# 4_ETHERNET.net
KiCad netlist of a schematic drawn in Altium Designer
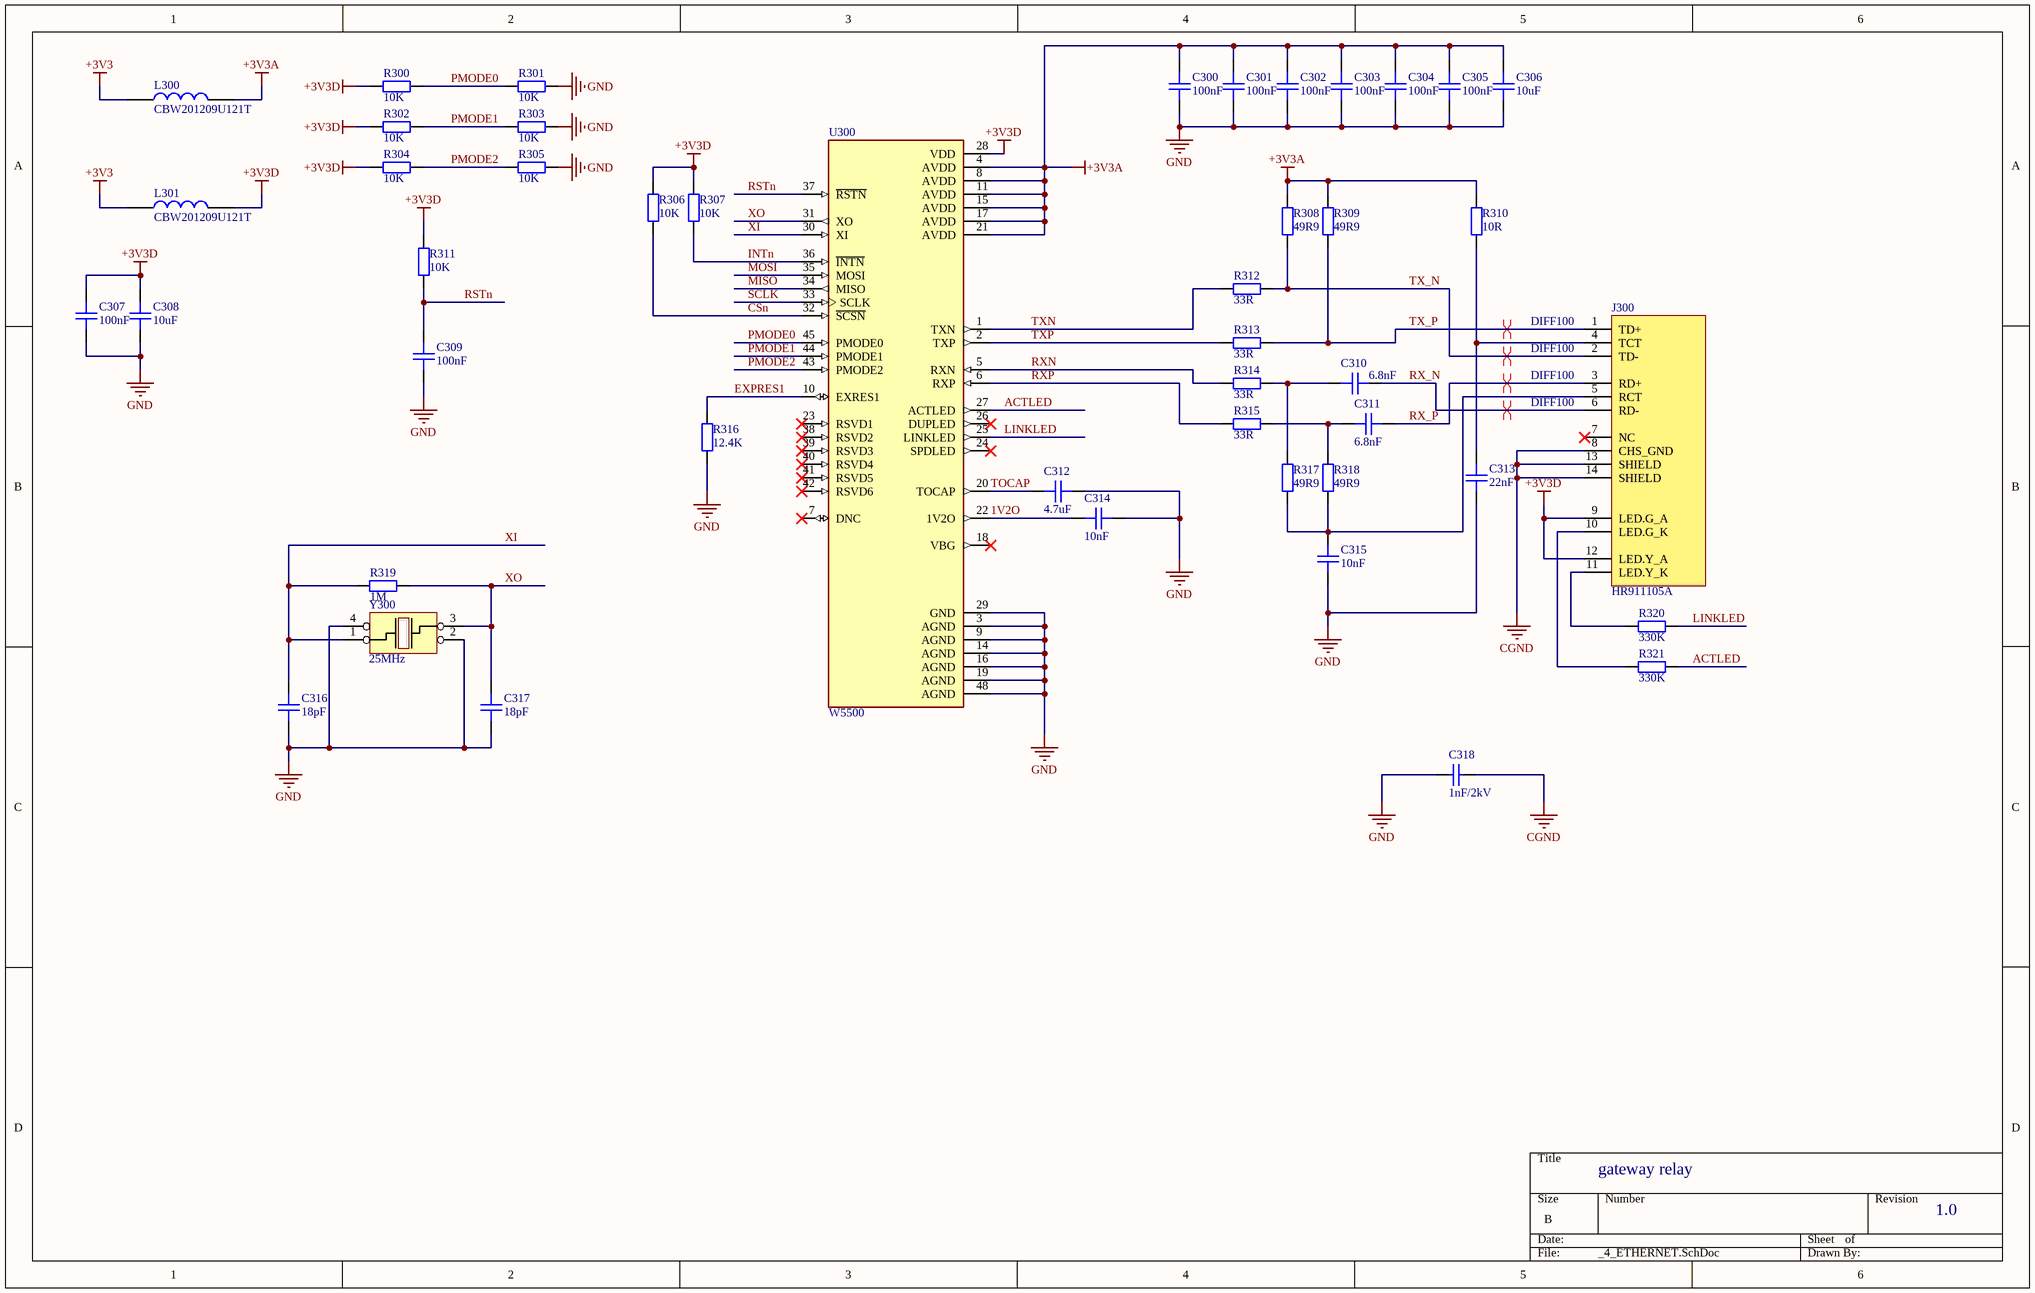
[diagram p0: _4_ETHERNET.SchDoc]

(export (version "E")
  (design (tool "Eeschema 10.0.6"))
  (components
    (comp (ref "C300")
      (value "100nF")
      (footprint "CAPC-0603 (1608)")
      (description "CAP CER 1uF 10% 16V X7R 0603")
      (fields (field (name "MPN") "CC0603KRX7R7BB105"))
      (libsource (lib "BYTECH_HW_LIB_2019") (part "CC0603KRX7R7BB105"))
    )
    (comp (ref "C301")
      (value "100nF")
      (footprint "CAPC-0603 (1608)")
      (description "CAP CER 1uF 10% 16V X7R 0603")
      (fields (field (name "MPN") "CC0603KRX7R7BB105"))
      (libsource (lib "BYTECH_HW_LIB_2019") (part "CC0603KRX7R7BB105"))
    )
    (comp (ref "C302")
      (value "100nF")
      (footprint "CAPC-0603 (1608)")
      (description "CAP CER 1uF 10% 16V X7R 0603")
      (fields (field (name "MPN") "CC0603KRX7R7BB105"))
      (libsource (lib "BYTECH_HW_LIB_2019") (part "CC0603KRX7R7BB105"))
    )
    (comp (ref "C303")
      (value "100nF")
      (footprint "CAPC-0603 (1608)")
      (description "CAP CER 1uF 10% 16V X7R 0603")
      (fields (field (name "MPN") "CC0603KRX7R7BB105"))
      (libsource (lib "BYTECH_HW_LIB_2019") (part "CC0603KRX7R7BB105"))
    )
    (comp (ref "C304")
      (value "100nF")
      (footprint "CAPC-0603 (1608)")
      (description "CAP CER 1uF 10% 16V X7R 0603")
      (fields (field (name "MPN") "CC0603KRX7R7BB105"))
      (libsource (lib "BYTECH_HW_LIB_2019") (part "CC0603KRX7R7BB105"))
    )
    (comp (ref "C305")
      (value "100nF")
      (footprint "CAPC-0603 (1608)")
      (description "CAP CER 1uF 10% 16V X7R 0603")
      (fields (field (name "MPN") "CC0603KRX7R7BB105"))
      (libsource (lib "BYTECH_HW_LIB_2019") (part "CC0603KRX7R7BB105"))
    )
    (comp (ref "C306")
      (value "10uF")
      (footprint "CAPC-0603 (1608)")
      (description "CAP CER 0.018UF 50V X7R 0603")
      (fields (field (name "MPN") "CC0603JRX7R9BB183") (field (name "MFR") "Yageo"))
      (libsource (lib "BYTECH_HW_LIB_2019") (part "CC0603JRX7R9BB183"))
    )
    (comp (ref "C307")
      (value "100nF")
      (footprint "CAPC-0603 (1608)")
      (description "CAP CER 1uF 10% 16V X7R 0603")
      (fields (field (name "MPN") "CC0603KRX7R7BB105"))
      (libsource (lib "BYTECH_HW_LIB_2019") (part "CC0603KRX7R7BB105"))
    )
    (comp (ref "C308")
      (value "10uF")
      (footprint "CAPC-0603 (1608)")
      (description "CAP CER 0.018UF 50V X7R 0603")
      (fields (field (name "MPN") "CC0603JRX7R9BB183") (field (name "MFR") "Yageo"))
      (libsource (lib "BYTECH_HW_LIB_2019") (part "CC0603JRX7R9BB183"))
    )
    (comp (ref "C309")
      (value "100nF")
      (footprint "CAPC-0603 (1608)")
      (description "CAP CER 1uF 10% 16V X7R 0603")
      (fields (field (name "MPN") "CC0603KRX7R7BB105"))
      (libsource (lib "BYTECH_HW_LIB_2019") (part "CC0603KRX7R7BB105"))
    )
    (comp (ref "C310")
      (value "6.8nF")
      (footprint "CAPC-0603 (1608)")
      (description "CAP CER 6.8nF 5% 50V X7R 0603")
      (fields (field (name "MPN") "CC0603JRX7R9BB682"))
      (libsource (lib "BYTECH_HW_LIB_2019") (part "CC0603JRX7R9BB682"))
    )
    (comp (ref "C311")
      (value "6.8nF")
      (footprint "CAPC-0603 (1608)")
      (description "CAP CER 6.8nF 5% 50V X7R 0603")
      (fields (field (name "MPN") "CC0603JRX7R9BB682"))
      (libsource (lib "BYTECH_HW_LIB_2019") (part "CC0603JRX7R9BB682"))
    )
    (comp (ref "C312")
      (value "4.7uF")
      (footprint "CAPC-0603 (1608)")
      (description "CAP CER 470pF 50V 5% C0G/NPO 0603")
      (fields (field (name "MPN") "CC0603JRNPO9BN471"))
      (libsource (lib "BYTECH_HW_LIB_2019") (part "CC0603JRNPO9BN471"))
    )
    (comp (ref "C313")
      (value "22nF")
      (footprint "CAPC-0603 (1608)")
      (description "CAP CER 0.22UF 16V X7R 0603")
      (fields (field (name "MPN") "CC0603KRX7R7BB224") (field (name "MFR") "Yageo"))
      (libsource (lib "BYTECH_HW_LIB_2019") (part "CC0603KRX7R7BB224"))
    )
    (comp (ref "C314")
      (value "10nF")
      (footprint "CAPC-0603 (1608)")
      (description "CAP CER 10nF 16V 10% X7R 0603")
      (fields (field (name "MPN") "CC0603KRX7R7BB103"))
      (libsource (lib "BYTECH_HW_LIB_2019") (part "CC0603KRX7R7BB103"))
    )
    (comp (ref "C315")
      (value "10nF")
      (footprint "CAPC-0603 (1608)")
      (description "CAP CER 10nF 16V 10% X7R 0603")
      (fields (field (name "MPN") "CC0603KRX7R7BB103"))
      (libsource (lib "BYTECH_HW_LIB_2019") (part "CC0603KRX7R7BB103"))
    )
    (comp (ref "C316")
      (value "18pF")
      (footprint "CAPC-0603 (1608)")
      (description "CAP CER 180PF 50V 5% COG/NPO 0603")
      (fields (field (name "MPN") "CC0603JRNPO9BN181"))
      (libsource (lib "BYTECH_HW_LIB_2019") (part "CC0603JRNPO9BN181"))
    )
    (comp (ref "C317")
      (value "18pF")
      (footprint "CAPC-0603 (1608)")
      (description "CAP CER 180PF 50V 5% COG/NPO 0603")
      (fields (field (name "MPN") "CC0603JRNPO9BN181"))
      (libsource (lib "BYTECH_HW_LIB_2019") (part "CC0603JRNPO9BN181"))
    )
    (comp (ref "C318")
      (value "1nF/2kV")
      (footprint "tu 1206")
      (description "Dán")
      (libsource (lib "Altium_Lib_by_KhueNguyenCreator") (part "Tu 1206 470pF 50V 10%"))
    )
    (comp (ref "J300")
      (value "HR911105A")
      (footprint "HR911105A")
      (description "Hanrun HR911105A RJ-45 Connector")
      (fields (field (name "MFR") "HanRun"))
      (libsource (lib "BYTECH_HW_LIB_2019") (part "HR911105A"))
    )
    (comp (ref "L300")
      (value "CBW201209U121T")
      (footprint "IND-0805 (2012)")
      (description "IND-FERRITE BEAD 220 OHM 0805 1LN")
      (fields (field (name "MPN") "MPZ2012S221A"))
      (libsource (lib "") (part "MPZ2012S221A_1"))
    )
    (comp (ref "L301")
      (value "CBW201209U121T")
      (footprint "IND-0805 (2012)")
      (description "IND-FERRITE BEAD 220 OHM 0805 1LN")
      (fields (field (name "MPN") "MPZ2012S221A"))
      (libsource (lib "BYTECH_HW_LIB_2019") (part "MPZ2012S221A"))
    )
    (comp (ref "R300")
      (value "10K")
      (footprint "RESC-0603 (1608)")
      (description "RES SMD 10K OHM 1% 1/10W 0603")
      (fields (field (name "MPN") "RC0603FR-0710KL"))
      (libsource (lib "BYTECH_HW_LIB_2019") (part "RC0603FR-0710KL"))
    )
    (comp (ref "R301")
      (value "10K")
      (footprint "RESC-0603 (1608)")
      (description "RES SMD 10K OHM 1% 1/10W 0603")
      (fields (field (name "MPN") "RC0603FR-0710KL"))
      (libsource (lib "BYTECH_HW_LIB_2019") (part "RC0603FR-0710KL"))
    )
    (comp (ref "R302")
      (value "10K")
      (footprint "RESC-0603 (1608)")
      (description "RES SMD 10K OHM 1% 1/10W 0603")
      (fields (field (name "MPN") "RC0603FR-0710KL"))
      (libsource (lib "BYTECH_HW_LIB_2019") (part "RC0603FR-0710KL"))
    )
    (comp (ref "R303")
      (value "10K")
      (footprint "RESC-0603 (1608)")
      (description "RES SMD 10K OHM 1% 1/10W 0603")
      (fields (field (name "MPN") "RC0603FR-0710KL"))
      (libsource (lib "BYTECH_HW_LIB_2019") (part "RC0603FR-0710KL"))
    )
    (comp (ref "R304")
      (value "10K")
      (footprint "RESC-0603 (1608)")
      (description "RES SMD 10K OHM 1% 1/10W 0603")
      (fields (field (name "MPN") "RC0603FR-0710KL"))
      (libsource (lib "BYTECH_HW_LIB_2019") (part "RC0603FR-0710KL"))
    )
    (comp (ref "R305")
      (value "10K")
      (footprint "RESC-0603 (1608)")
      (description "RES SMD 10K OHM 1% 1/10W 0603")
      (fields (field (name "MPN") "RC0603FR-0710KL"))
      (libsource (lib "BYTECH_HW_LIB_2019") (part "RC0603FR-0710KL"))
    )
    (comp (ref "R306")
      (value "10K")
      (footprint "RESC-0603 (1608)")
      (description "RES SMD 10K OHM 1% 1/10W 0603")
      (fields (field (name "MPN") "RC0603FR-0710KL"))
      (libsource (lib "") (part "RC0603FR-0710KL_1"))
    )
    (comp (ref "R307")
      (value "10K")
      (footprint "RESC-0603 (1608)")
      (description "RES SMD 10K OHM 1% 1/10W 0603")
      (fields (field (name "MPN") "RC0603FR-0710KL"))
      (libsource (lib "") (part "RC0603FR-0710KL_1"))
    )
    (comp (ref "R308")
      (value "49R9")
      (footprint "RESC-0603 (1608)")
      (description "RES SMD 49.9 OHM 1% 1/10W 0603")
      (fields (field (name "MPN") "RC0603FR-0749R9L") (field (name "MFR") "Yageo"))
      (libsource (lib "BYTECH_HW_LIB_2019") (part "RC0603FR-0749R9L"))
    )
    (comp (ref "R309")
      (value "49R9")
      (footprint "RESC-0603 (1608)")
      (description "RES SMD 49.9 OHM 1% 1/10W 0603")
      (fields (field (name "MPN") "RC0603FR-0749R9L") (field (name "MFR") "Yageo"))
      (libsource (lib "BYTECH_HW_LIB_2019") (part "RC0603FR-0749R9L"))
    )
    (comp (ref "R310")
      (value "10R")
      (footprint "RESC-0603 (1608)")
      (description "RES SMD 10 OHM 1% 1/10W 0603")
      (fields (field (name "MPN") "RC0603FR-0710RL"))
      (libsource (lib "BYTECH_HW_LIB_2019") (part "RC0603FR-0710RL"))
    )
    (comp (ref "R311")
      (value "10K")
      (footprint "RESC-0603 (1608)")
      (description "RES SMD 10K OHM 1% 1/10W 0603")
      (fields (field (name "MPN") "RC0603FR-0710KL"))
      (libsource (lib "") (part "RC0603FR-0710KL_1"))
    )
    (comp (ref "R312")
      (value "33R")
      (footprint "RESC-0603 (1608)")
      (description "RES SMD 33 OHM 1% 1/10W 0603")
      (fields (field (name "MPN") "RC0603FR-0733RL") (field (name "MFR") "Yageo"))
      (libsource (lib "BYTECH_HW_LIB_2019") (part "RC0603FR-0733RL"))
    )
    (comp (ref "R313")
      (value "33R")
      (footprint "RESC-0603 (1608)")
      (description "RES SMD 33 OHM 1% 1/10W 0603")
      (fields (field (name "MPN") "RC0603FR-0733RL") (field (name "MFR") "Yageo"))
      (libsource (lib "BYTECH_HW_LIB_2019") (part "RC0603FR-0733RL"))
    )
    (comp (ref "R314")
      (value "33R")
      (footprint "RESC-0603 (1608)")
      (description "RES SMD 33 OHM 1% 1/10W 0603")
      (fields (field (name "MPN") "RC0603FR-0733RL") (field (name "MFR") "Yageo"))
      (libsource (lib "BYTECH_HW_LIB_2019") (part "RC0603FR-0733RL"))
    )
    (comp (ref "R315")
      (value "33R")
      (footprint "RESC-0603 (1608)")
      (description "RES SMD 33 OHM 1% 1/10W 0603")
      (fields (field (name "MPN") "RC0603FR-0733RL") (field (name "MFR") "Yageo"))
      (libsource (lib "BYTECH_HW_LIB_2019") (part "RC0603FR-0733RL"))
    )
    (comp (ref "R316")
      (value "12.4K")
      (footprint "RESC-0603 (1608)")
      (description "RES SMD 12KOHM 1% 1/10W 0603")
      (fields (field (name "MPN") "RC0603FR-0712KL"))
      (libsource (lib "BYTECH_HW_LIB_2019") (part "RC0603FR-0712KL"))
    )
    (comp (ref "R317")
      (value "49R9")
      (footprint "RESC-0603 (1608)")
      (description "RES SMD 49.9 OHM 1% 1/10W 0603")
      (fields (field (name "MPN") "RC0603FR-0749R9L") (field (name "MFR") "Yageo"))
      (libsource (lib "BYTECH_HW_LIB_2019") (part "RC0603FR-0749R9L"))
    )
    (comp (ref "R318")
      (value "49R9")
      (footprint "RESC-0603 (1608)")
      (description "RES SMD 49.9 OHM 1% 1/10W 0603")
      (fields (field (name "MPN") "RC0603FR-0749R9L") (field (name "MFR") "Yageo"))
      (libsource (lib "BYTECH_HW_LIB_2019") (part "RC0603FR-0749R9L"))
    )
    (comp (ref "R319")
      (value "1M")
      (footprint "RESC-0603 (1608)")
      (description "RES SMD 10M OHM 1% 1/10W 0603")
      (fields (field (name "MPN") "RC0603FR-0710ML"))
      (libsource (lib "BYTECH_HW_LIB_2019") (part "RC0603FR-0710ML"))
    )
    (comp (ref "R320")
      (value "330K")
      (footprint "RESC-0603 (1608)")
      (description "RES SMD 330K OHM 1% 1/10W 0603")
      (fields (field (name "MPN") "RC0603FR-07330KL"))
      (libsource (lib "BYTECH_HW_LIB_2019") (part "RC0603FR-07330KL"))
    )
    (comp (ref "R321")
      (value "330K")
      (footprint "RESC-0603 (1608)")
      (description "RES SMD 330K OHM 1% 1/10W 0603")
      (fields (field (name "MPN") "RC0603FR-07330KL"))
      (libsource (lib "BYTECH_HW_LIB_2019") (part "RC0603FR-07330KL"))
    )
    (comp (ref "U300")
      (value "W5500")
      (footprint "QFP50P900X900X160-48N")
      (description "Hardwired TCP/IP embedded Ethernet controller")
      (libsource (lib "W5500") (part "W5500"))
    )
    (comp (ref "Y300")
      (value "25MHz")
      (footprint "CRYSTALL_SMD_3225")
      (description "CRYSTAL 25.0000MHZ 18PF SMD")
      (fields (field (name "MPN") "ABM8G-25.000MHZ-18-D2Y-T") (field (name "MFR") "Abracon LLC"))
      (libsource (lib "BYTECH_HW_LIB_2019") (part "ABM8G-25.000MHZ-18-D2Y-T"))
    )
  )
  (nets
    (net (code "1") (name "+3V3") (class "Default")
      (node (ref "L300") (pin "2") (pinfunction "2_2") (pintype "passive"))
      (node (ref "L301") (pin "1") (pinfunction "1_1") (pintype "passive"))
    )
    (net (code "2") (name "+3V3A") (class "Default")
      (node (ref "C300") (pin "2") (pinfunction "2_2") (pintype "passive"))
      (node (ref "C301") (pin "2") (pinfunction "2_2") (pintype "passive"))
      (node (ref "C302") (pin "2") (pinfunction "2_2") (pintype "passive"))
      (node (ref "C303") (pin "2") (pinfunction "2_2") (pintype "passive"))
      (node (ref "C304") (pin "2") (pinfunction "2_2") (pintype "passive"))
      (node (ref "C305") (pin "2") (pinfunction "2_2") (pintype "passive"))
      (node (ref "C306") (pin "2") (pinfunction "2_2") (pintype "passive"))
      (node (ref "L300") (pin "1") (pinfunction "1_1") (pintype "passive"))
      (node (ref "R308") (pin "2") (pinfunction "2_2") (pintype "passive"))
      (node (ref "R309") (pin "2") (pinfunction "2_2") (pintype "passive"))
      (node (ref "R310") (pin "2") (pinfunction "2_2") (pintype "passive"))
      (node (ref "U300") (pin "11") (pinfunction "AVDD_11") (pintype "power_in"))
      (node (ref "U300") (pin "15") (pinfunction "AVDD_15") (pintype "power_in"))
      (node (ref "U300") (pin "17") (pinfunction "AVDD_17") (pintype "power_in"))
      (node (ref "U300") (pin "21") (pinfunction "AVDD_21") (pintype "power_in"))
      (node (ref "U300") (pin "4") (pinfunction "AVDD_4") (pintype "power_in"))
      (node (ref "U300") (pin "8") (pinfunction "AVDD_8") (pintype "power_in"))
    )
    (net (code "3") (name "+3V3D") (class "Default")
      (node (ref "C307") (pin "2") (pinfunction "2_2") (pintype "passive"))
      (node (ref "C308") (pin "2") (pinfunction "2_2") (pintype "passive"))
      (node (ref "J300") (pin "12") (pinfunction "LED.Y_A_12") (pintype "passive"))
      (node (ref "J300") (pin "9") (pinfunction "LED.G_A_9") (pintype "passive"))
      (node (ref "L301") (pin "2") (pinfunction "2_2") (pintype "passive"))
      (node (ref "R300") (pin "1") (pinfunction "1_1") (pintype "passive"))
      (node (ref "R302") (pin "1") (pinfunction "1_1") (pintype "passive"))
      (node (ref "R304") (pin "1") (pinfunction "1_1") (pintype "passive"))
      (node (ref "R306") (pin "2") (pinfunction "2_2") (pintype "passive"))
      (node (ref "R307") (pin "2") (pinfunction "2_2") (pintype "passive"))
      (node (ref "R311") (pin "2") (pinfunction "2_2") (pintype "passive"))
      (node (ref "U300") (pin "28") (pinfunction "VDD_28") (pintype "power_in"))
    )
    (net (code "4") (name "/1V2O") (class "Default")
      (node (ref "C314") (pin "1") (pinfunction "1_1") (pintype "passive"))
      (node (ref "U300") (pin "22") (pinfunction "1V2O_22") (pintype "output"))
    )
    (net (code "5") (name "/ACTLED") (class "Default")
      (node (ref "R321") (pin "2") (pinfunction "2_2") (pintype "passive"))
      (node (ref "U300") (pin "27") (pinfunction "ACTLED_27") (pintype "output"))
    )
    (net (code "6") (name "/CSn") (class "Default")
      (node (ref "R306") (pin "1") (pinfunction "1_1") (pintype "passive"))
      (node (ref "U300") (pin "32") (pinfunction "~{SCSN}_32") (pintype "input"))
    )
    (net (code "7") (name "/EXPRES1") (class "Default")
      (node (ref "R316") (pin "2") (pinfunction "2_2") (pintype "passive"))
      (node (ref "U300") (pin "10") (pinfunction "EXRES1_10") (pintype "bidirectional"))
    )
    (net (code "8") (name "/INTn") (class "Default")
      (node (ref "R307") (pin "1") (pinfunction "1_1") (pintype "passive"))
      (node (ref "U300") (pin "36") (pinfunction "~{INTN}_36") (pintype "input"))
    )
    (net (code "9") (name "/LINKLED") (class "Default")
      (node (ref "R320") (pin "2") (pinfunction "2_2") (pintype "passive"))
      (node (ref "U300") (pin "25") (pinfunction "LINKLED_25") (pintype "output"))
    )
    (net (code "10") (name "/MISO") (class "Default")
      (node (ref "U300") (pin "34") (pinfunction "MISO_34") (pintype "output"))
    )
    (net (code "11") (name "/MOSI") (class "Default")
      (node (ref "U300") (pin "35") (pinfunction "MOSI_35") (pintype "input"))
    )
    (net (code "12") (name "/PMODE0") (class "Default")
      (node (ref "R300") (pin "2") (pinfunction "2_2") (pintype "passive"))
      (node (ref "R301") (pin "1") (pinfunction "1_1") (pintype "passive"))
      (node (ref "U300") (pin "45") (pinfunction "PMODE0_45") (pintype "input"))
    )
    (net (code "13") (name "/PMODE1") (class "Default")
      (node (ref "R302") (pin "2") (pinfunction "2_2") (pintype "passive"))
      (node (ref "R303") (pin "1") (pinfunction "1_1") (pintype "passive"))
      (node (ref "U300") (pin "44") (pinfunction "PMODE1_44") (pintype "input"))
    )
    (net (code "14") (name "/PMODE2") (class "Default")
      (node (ref "R304") (pin "2") (pinfunction "2_2") (pintype "passive"))
      (node (ref "R305") (pin "1") (pinfunction "1_1") (pintype "passive"))
      (node (ref "U300") (pin "43") (pinfunction "PMODE2_43") (pintype "input"))
    )
    (net (code "15") (name "/RSTn") (class "Default")
      (node (ref "C309") (pin "2") (pinfunction "2_2") (pintype "passive"))
      (node (ref "R311") (pin "1") (pinfunction "1_1") (pintype "passive"))
      (node (ref "U300") (pin "37") (pinfunction "~{RSTN}_37") (pintype "input"))
    )
    (net (code "16") (name "/RXN") (class "Default")
      (node (ref "R314") (pin "1") (pinfunction "1_1") (pintype "passive"))
      (node (ref "U300") (pin "5") (pinfunction "RXN_5") (pintype "input"))
    )
    (net (code "17") (name "/RXP") (class "Default")
      (node (ref "R315") (pin "1") (pinfunction "1_1") (pintype "passive"))
      (node (ref "U300") (pin "6") (pinfunction "RXP_6") (pintype "input"))
    )
    (net (code "18") (name "/RX_N") (class "Default")
      (node (ref "C310") (pin "2") (pinfunction "2_2") (pintype "passive"))
      (node (ref "J300") (pin "6") (pinfunction "RD-_6") (pintype "passive"))
    )
    (net (code "19") (name "/RX_P") (class "Default")
      (node (ref "C311") (pin "2") (pinfunction "2_2") (pintype "passive"))
      (node (ref "J300") (pin "3") (pinfunction "RD+_3") (pintype "passive"))
    )
    (net (code "20") (name "/SCLK") (class "Default")
      (node (ref "U300") (pin "33") (pinfunction "SCLK_33") (pintype "input"))
    )
    (net (code "21") (name "/TOCAP") (class "Default")
      (node (ref "C312") (pin "1") (pinfunction "1_1") (pintype "passive"))
      (node (ref "U300") (pin "20") (pinfunction "TOCAP_20") (pintype "output"))
    )
    (net (code "22") (name "/TXN") (class "Default")
      (node (ref "R312") (pin "1") (pinfunction "1_1") (pintype "passive"))
      (node (ref "U300") (pin "1") (pinfunction "TXN_1") (pintype "output"))
    )
    (net (code "23") (name "/TXP") (class "Default")
      (node (ref "R313") (pin "1") (pinfunction "1_1") (pintype "passive"))
      (node (ref "U300") (pin "2") (pinfunction "TXP_2") (pintype "output"))
    )
    (net (code "24") (name "/TX_N") (class "Default")
      (node (ref "J300") (pin "2") (pinfunction "TD-_2") (pintype "passive"))
      (node (ref "R308") (pin "1") (pinfunction "1_1") (pintype "passive"))
      (node (ref "R312") (pin "2") (pinfunction "2_2") (pintype "passive"))
    )
    (net (code "25") (name "/TX_P") (class "Default")
      (node (ref "J300") (pin "1") (pinfunction "TD+_1") (pintype "passive"))
      (node (ref "R309") (pin "1") (pinfunction "1_1") (pintype "passive"))
      (node (ref "R313") (pin "2") (pinfunction "2_2") (pintype "passive"))
    )
    (net (code "26") (name "/XI") (class "Default")
      (node (ref "C316") (pin "2") (pinfunction "2_2") (pintype "passive"))
      (node (ref "R319") (pin "1") (pinfunction "1_1") (pintype "passive"))
      (node (ref "U300") (pin "30") (pinfunction "XI_30") (pintype "input"))
      (node (ref "Y300") (pin "1") (pinfunction "1_1") (pintype "passive"))
    )
    (net (code "27") (name "/XO") (class "Default")
      (node (ref "C317") (pin "2") (pinfunction "2_2") (pintype "passive"))
      (node (ref "R319") (pin "2") (pinfunction "2_2") (pintype "passive"))
      (node (ref "U300") (pin "31") (pinfunction "XO_31") (pintype "output"))
      (node (ref "Y300") (pin "3") (pinfunction "3_3") (pintype "passive"))
    )
    (net (code "28") (name "CGND") (class "Default")
      (node (ref "C318") (pin "1") (pinfunction "1_1") (pintype "passive"))
      (node (ref "J300") (pin "13") (pinfunction "SHIELD_13") (pintype "passive"))
      (node (ref "J300") (pin "14") (pinfunction "SHIELD_14") (pintype "passive"))
      (node (ref "J300") (pin "8") (pinfunction "CHS_GND_8") (pintype "passive"))
    )
    (net (code "29") (name "GND") (class "Default")
      (node (ref "C300") (pin "1") (pinfunction "1_1") (pintype "passive"))
      (node (ref "C301") (pin "1") (pinfunction "1_1") (pintype "passive"))
      (node (ref "C302") (pin "1") (pinfunction "1_1") (pintype "passive"))
      (node (ref "C303") (pin "1") (pinfunction "1_1") (pintype "passive"))
      (node (ref "C304") (pin "1") (pinfunction "1_1") (pintype "passive"))
      (node (ref "C305") (pin "1") (pinfunction "1_1") (pintype "passive"))
      (node (ref "C306") (pin "1") (pinfunction "1_1") (pintype "passive"))
      (node (ref "C307") (pin "1") (pinfunction "1_1") (pintype "passive"))
      (node (ref "C308") (pin "1") (pinfunction "1_1") (pintype "passive"))
      (node (ref "C309") (pin "1") (pinfunction "1_1") (pintype "passive"))
      (node (ref "C312") (pin "2") (pinfunction "2_2") (pintype "passive"))
      (node (ref "C313") (pin "1") (pinfunction "1_1") (pintype "passive"))
      (node (ref "C314") (pin "2") (pinfunction "2_2") (pintype "passive"))
      (node (ref "C315") (pin "1") (pinfunction "1_1") (pintype "passive"))
      (node (ref "C316") (pin "1") (pinfunction "1_1") (pintype "passive"))
      (node (ref "C317") (pin "1") (pinfunction "1_1") (pintype "passive"))
      (node (ref "C318") (pin "2") (pinfunction "2_2") (pintype "passive"))
      (node (ref "R301") (pin "2") (pinfunction "2_2") (pintype "passive"))
      (node (ref "R303") (pin "2") (pinfunction "2_2") (pintype "passive"))
      (node (ref "R305") (pin "2") (pinfunction "2_2") (pintype "passive"))
      (node (ref "R316") (pin "1") (pinfunction "1_1") (pintype "passive"))
      (node (ref "U300") (pin "14") (pinfunction "AGND_14") (pintype "power_in"))
      (node (ref "U300") (pin "16") (pinfunction "AGND_16") (pintype "power_in"))
      (node (ref "U300") (pin "19") (pinfunction "AGND_19") (pintype "power_in"))
      (node (ref "U300") (pin "29") (pinfunction "GND_29") (pintype "passive"))
      (node (ref "U300") (pin "3") (pinfunction "AGND_3") (pintype "power_in"))
      (node (ref "U300") (pin "48") (pinfunction "AGND_48") (pintype "power_in"))
      (node (ref "U300") (pin "9") (pinfunction "AGND_9") (pintype "power_in"))
      (node (ref "Y300") (pin "2") (pinfunction "2_2") (pintype "passive"))
      (node (ref "Y300") (pin "4") (pinfunction "4_4") (pintype "passive"))
    )
    (net (code "30") (name "Net-(C310-Pad1)") (class "Default")
      (node (ref "C310") (pin "1") (pinfunction "1_1") (pintype "passive"))
      (node (ref "R314") (pin "2") (pinfunction "2_2") (pintype "passive"))
      (node (ref "R317") (pin "2") (pinfunction "2_2") (pintype "passive"))
    )
    (net (code "31") (name "Net-(C311-Pad1)") (class "Default")
      (node (ref "C311") (pin "1") (pinfunction "1_1") (pintype "passive"))
      (node (ref "R315") (pin "2") (pinfunction "2_2") (pintype "passive"))
      (node (ref "R318") (pin "2") (pinfunction "2_2") (pintype "passive"))
    )
    (net (code "32") (name "Net-(J300-LED.G_K)") (class "Default")
      (node (ref "J300") (pin "10") (pinfunction "LED.G_K_10") (pintype "passive"))
      (node (ref "R321") (pin "1") (pinfunction "1_1") (pintype "passive"))
    )
    (net (code "33") (name "Net-(J300-LED.Y_K)") (class "Default")
      (node (ref "J300") (pin "11") (pinfunction "LED.Y_K_11") (pintype "passive"))
      (node (ref "R320") (pin "1") (pinfunction "1_1") (pintype "passive"))
    )
    (net (code "34") (name "Net-(J300-RCT)") (class "Default")
      (node (ref "C315") (pin "2") (pinfunction "2_2") (pintype "passive"))
      (node (ref "J300") (pin "5") (pinfunction "RCT_5") (pintype "passive"))
      (node (ref "R317") (pin "1") (pinfunction "1_1") (pintype "passive"))
      (node (ref "R318") (pin "1") (pinfunction "1_1") (pintype "passive"))
    )
    (net (code "35") (name "Net-(J300-TCT)") (class "Default")
      (node (ref "C313") (pin "2") (pinfunction "2_2") (pintype "passive"))
      (node (ref "J300") (pin "4") (pinfunction "TCT_4") (pintype "passive"))
      (node (ref "R310") (pin "1") (pinfunction "1_1") (pintype "passive"))
    )
    (net (code "36") (name "unconnected-(J300-NC-Pad7)") (class "Default")
      (node (ref "J300") (pin "7") (pinfunction "NC_7") (pintype "passive+no_connect"))
    )
    (net (code "37") (name "unconnected-(U300-DNC-Pad7)") (class "Default")
      (node (ref "U300") (pin "7") (pinfunction "DNC_7") (pintype "bidirectional+no_connect"))
    )
    (net (code "38") (name "unconnected-(U300-DUPLED-Pad26)") (class "Default")
      (node (ref "U300") (pin "26") (pinfunction "DUPLED_26") (pintype "output+no_connect"))
    )
    (net (code "39") (name "unconnected-(U300-RSVD1-Pad23)") (class "Default")
      (node (ref "U300") (pin "23") (pinfunction "RSVD1_23") (pintype "input+no_connect"))
    )
    (net (code "40") (name "unconnected-(U300-RSVD2-Pad38)") (class "Default")
      (node (ref "U300") (pin "38") (pinfunction "RSVD2_38") (pintype "input+no_connect"))
    )
    (net (code "41") (name "unconnected-(U300-RSVD3-Pad39)") (class "Default")
      (node (ref "U300") (pin "39") (pinfunction "RSVD3_39") (pintype "input+no_connect"))
    )
    (net (code "42") (name "unconnected-(U300-RSVD4-Pad40)") (class "Default")
      (node (ref "U300") (pin "40") (pinfunction "RSVD4_40") (pintype "input+no_connect"))
    )
    (net (code "43") (name "unconnected-(U300-RSVD5-Pad41)") (class "Default")
      (node (ref "U300") (pin "41") (pinfunction "RSVD5_41") (pintype "input+no_connect"))
    )
    (net (code "44") (name "unconnected-(U300-RSVD6-Pad42)") (class "Default")
      (node (ref "U300") (pin "42") (pinfunction "RSVD6_42") (pintype "input+no_connect"))
    )
    (net (code "45") (name "unconnected-(U300-SPDLED-Pad24)") (class "Default")
      (node (ref "U300") (pin "24") (pinfunction "SPDLED_24") (pintype "output+no_connect"))
    )
    (net (code "46") (name "unconnected-(U300-VBG-Pad18)") (class "Default")
      (node (ref "U300") (pin "18") (pinfunction "VBG_18") (pintype "output+no_connect"))
    )
  )
)
